# AIO_m_re_robotique_V3_2-PcPortableDany.net
KiCad netlist of a schematic drawn in EasyEDA
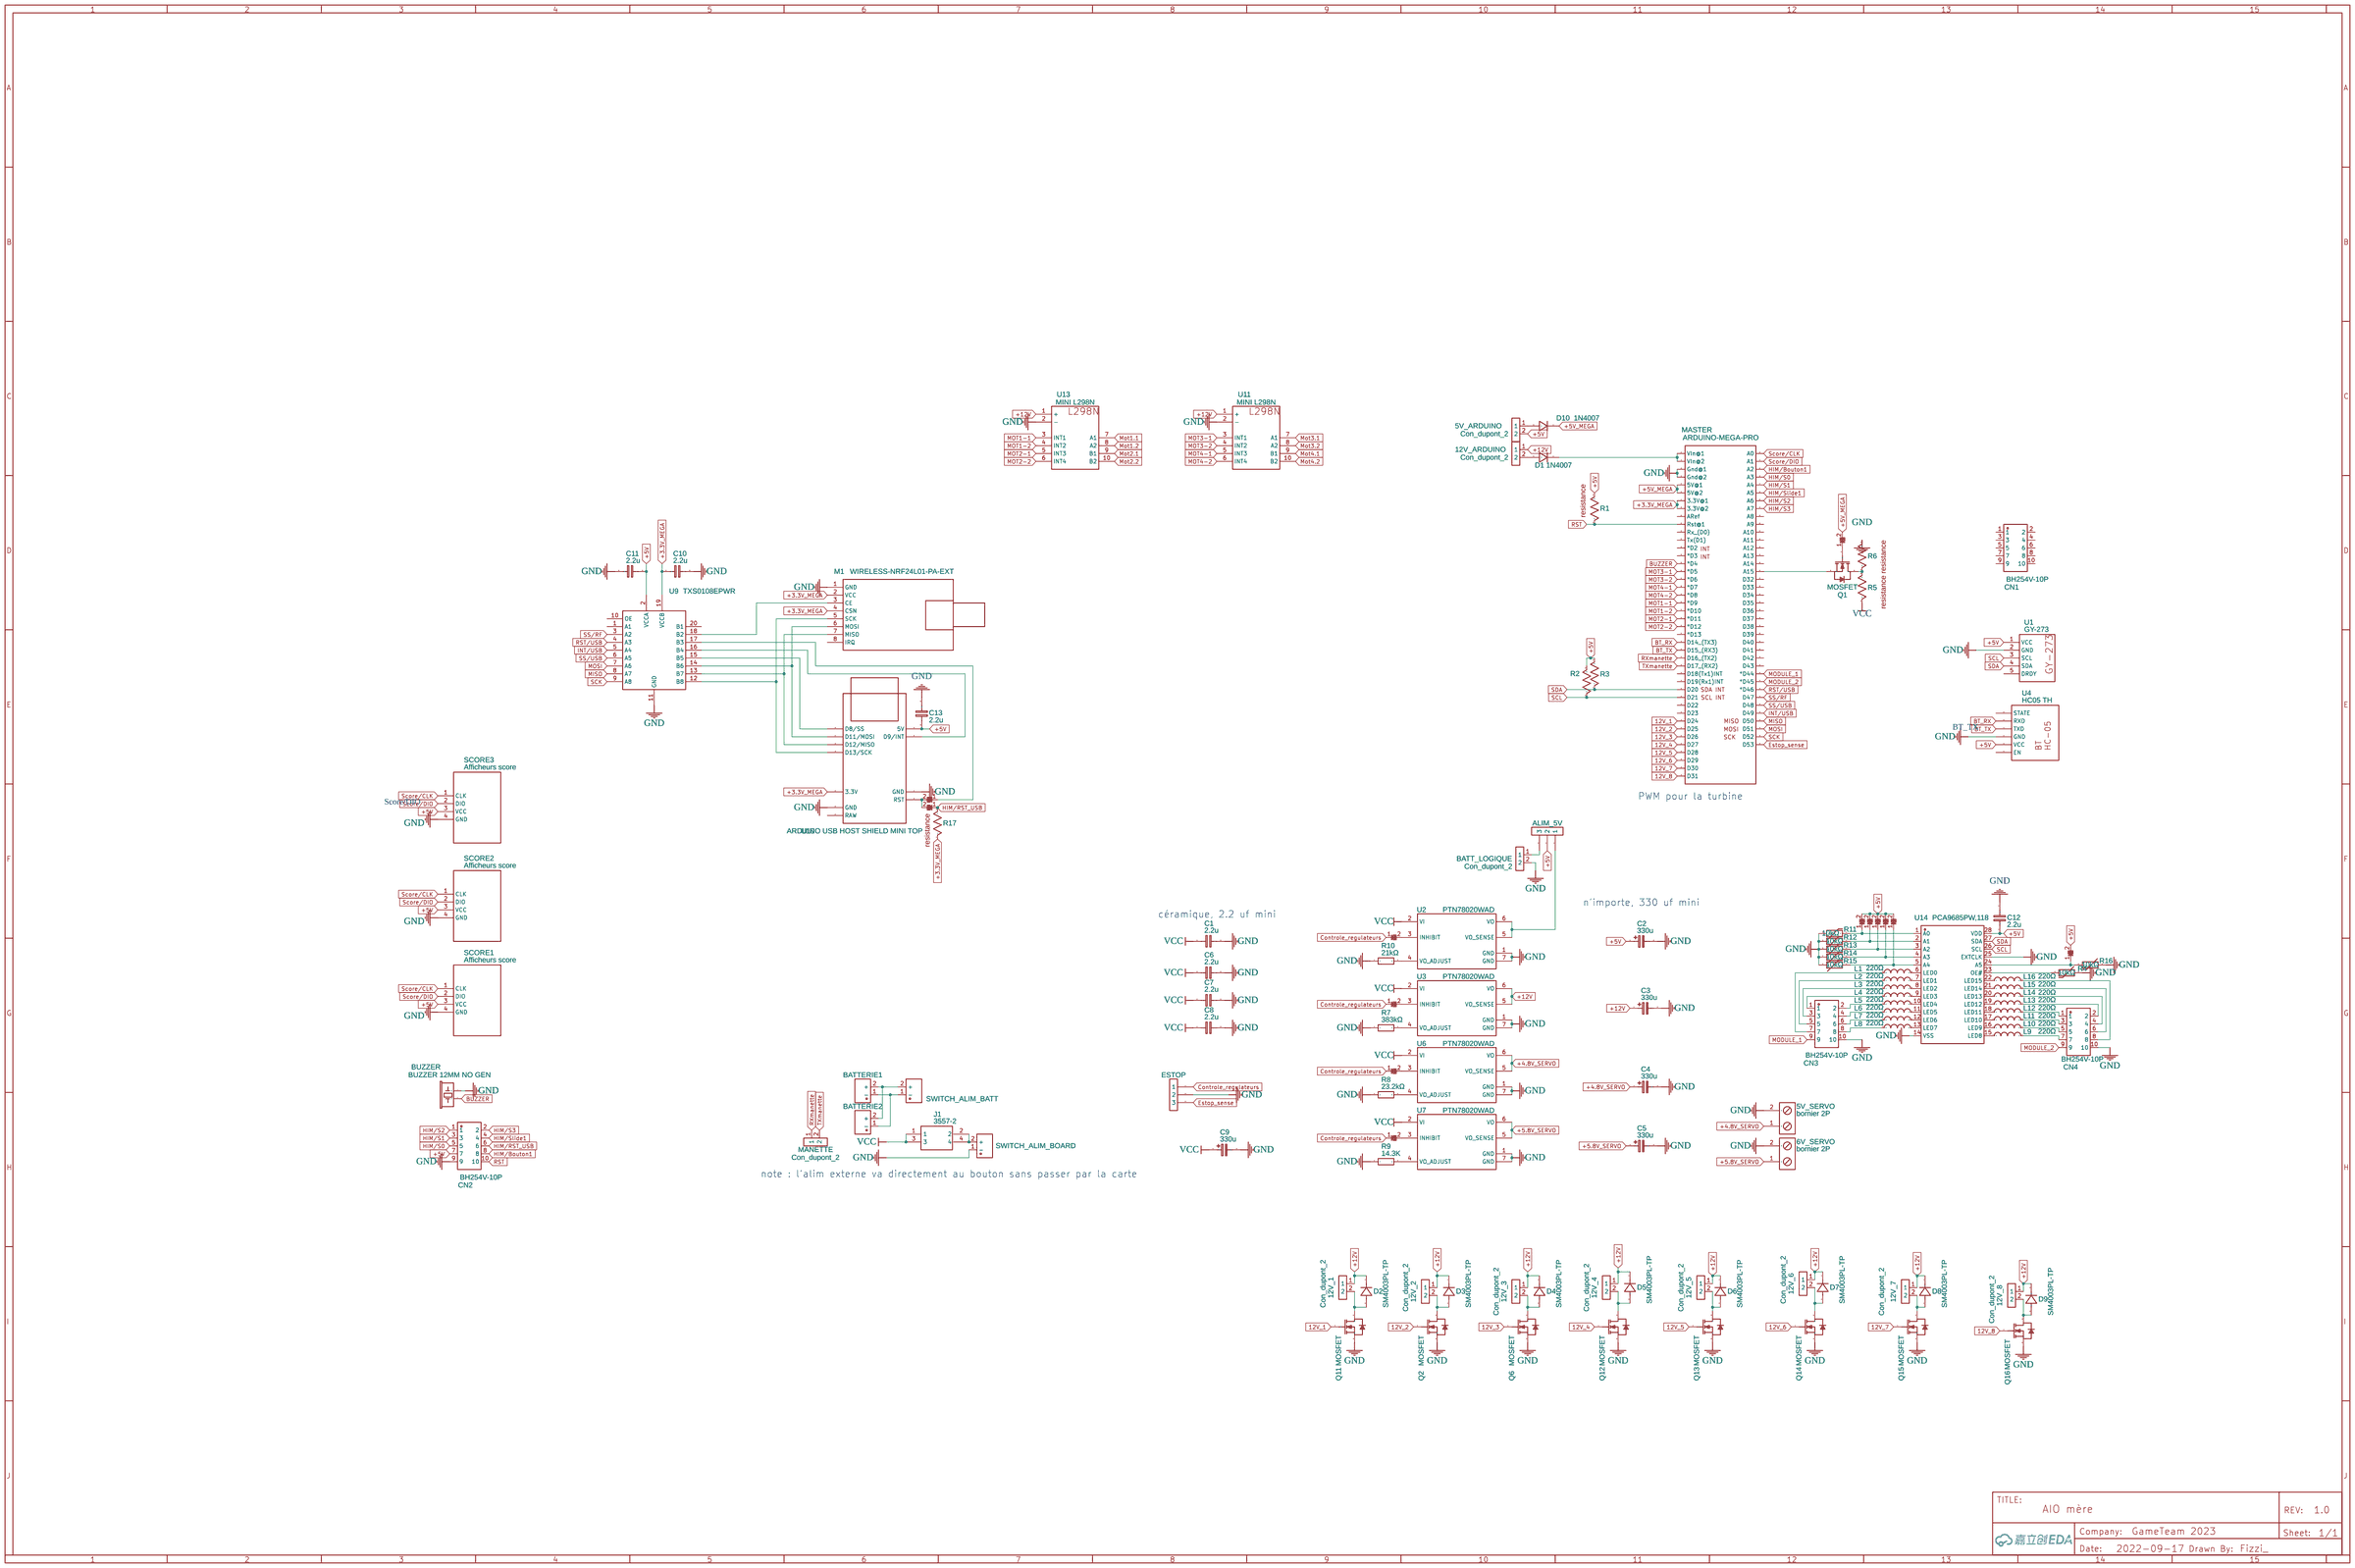
[diagram p0: schematic sheet]

(export (version "E")
  (design (tool "Eeschema 10.0.6"))
  (components
    (comp (ref "5V_ARDUINO") (value "Con_dupont_2") (libsource (lib "") (part "Con_dupont_2_2")))
    (comp (ref "5V_SERVO")
      (value "bornier 2P")
      (fields (field (name "BOM_Manufacturer Part") "bornier"))
      (libsource (lib "") (part "bornier 2P"))
    )
    (comp (ref "6V_SERVO")
      (value "bornier 2P")
      (fields (field (name "BOM_Manufacturer Part") "bornier"))
      (libsource (lib "") (part "bornier 2P_1"))
    )
    (comp (ref "12V_1") (value "Con_dupont_2") (libsource (lib "") (part "Con_dupont_2_1")))
    (comp (ref "12V_2") (value "Con_dupont_2") (libsource (lib "") (part "Con_dupont_2_1")))
    (comp (ref "12V_3") (value "Con_dupont_2") (libsource (lib "") (part "Con_dupont_2_1")))
    (comp (ref "12V_4") (value "Con_dupont_2") (libsource (lib "") (part "Con_dupont_2_1")))
    (comp (ref "12V_5") (value "Con_dupont_2") (libsource (lib "") (part "Con_dupont_2_1")))
    (comp (ref "12V_6") (value "Con_dupont_2") (libsource (lib "") (part "Con_dupont_2_1")))
    (comp (ref "12V_7") (value "Con_dupont_2") (libsource (lib "") (part "Con_dupont_2_1")))
    (comp (ref "12V_8") (value "Con_dupont_2") (libsource (lib "") (part "Con_dupont_2_1")))
    (comp (ref "12V_ARDUINO") (value "Con_dupont_2") (libsource (lib "") (part "Con_dupont_2_4")))
    (comp (ref "ALIM_5V") (value "Dupont 3Pin") (libsource (lib "") (part "Dupont 3Pin")))
    (comp (ref "BATTERIE1")
      (value "XT60-M")
      (fields
        (field (name "BOM_Manufacturer Part") "XT60UPB-M")
        (field (name "BOM_Supplier Part") "C2918078")
      )
      (libsource (lib "") (part "XT60-M_1"))
    )
    (comp (ref "BATTERIE2")
      (value "XT60-M")
      (fields
        (field (name "BOM_Manufacturer Part") "XT60UPB-M")
        (field (name "BOM_Supplier Part") "C2918078")
      )
      (libsource (lib "") (part "XT60-M_1"))
    )
    (comp (ref "BATT_LOGIQUE") (value "Con_dupont_2") (libsource (lib "") (part "Con_dupont_2_3")))
    (comp (ref "BUZZER") (value "BUZZER 12MM NO GEN") (libsource (lib "") (part "BUZZER 12MM NO GEN")))
    (comp (ref "BYPASS1") (value "SolderJumper") (libsource (lib "") (part "SolderJumperSmd6030")))
    (comp (ref "BYPASS2") (value "SolderJumper") (libsource (lib "") (part "SolderJumperSmd6030")))
    (comp (ref "BYPASS3") (value "SolderJumper") (libsource (lib "") (part "SolderJumperSmd6030")))
    (comp (ref "BYPASS4") (value "SolderJumper") (libsource (lib "") (part "SolderJumperSmd6030")))
    (comp (ref "BYPASS5") (value "SolderJumper") (libsource (lib "") (part "SolderJumperSmd6030")))
    (comp (ref "BYPASS6") (value "SolderJumper") (libsource (lib "") (part "SolderJumperSmd6030")))
    (comp (ref "BYPASS7") (value "SolderJumper") (libsource (lib "") (part "SolderJumperSmd6030")))
    (comp (ref "BYPASS8") (value "SolderJumper") (libsource (lib "") (part "SolderJumperSmd6030_2")))
    (comp (ref "BYPASS9") (value "SolderJumper") (libsource (lib "") (part "SolderJumperSmd6030_2")))
    (comp (ref "C1") (value "2.2u") (libsource (lib "") (part "C_0805_EU_1")))
    (comp (ref "C2") (value "330u") (libsource (lib "") (part "CE_TH_D8.0×F3.5_EU")))
    (comp (ref "C3") (value "330u") (libsource (lib "") (part "CE_TH_D8.0×F3.5_EU")))
    (comp (ref "C4") (value "330u") (libsource (lib "") (part "CE_TH_D8.0×F3.5_EU")))
    (comp (ref "C5") (value "330u") (libsource (lib "") (part "CE_TH_D8.0×F3.5_EU")))
    (comp (ref "C6") (value "2.2u") (libsource (lib "") (part "C_0805_EU_1")))
    (comp (ref "C7") (value "2.2u") (libsource (lib "") (part "C_0805_EU_1")))
    (comp (ref "C8") (value "2.2u") (libsource (lib "") (part "C_0805_EU_1")))
    (comp (ref "C9") (value "330u") (libsource (lib "") (part "CE_TH_D8.0×F3.5_EU")))
    (comp (ref "C10") (value "2.2u") (libsource (lib "") (part "C_0805_EU")))
    (comp (ref "C11") (value "2.2u") (libsource (lib "") (part "C_0805_EU")))
    (comp (ref "C12") (value "2.2u") (libsource (lib "") (part "C_0805_EU_2")))
    (comp (ref "C13") (value "2.2u") (libsource (lib "") (part "C_0805_EU_3")))
    (comp (ref "CN1")
      (value "BH254V-10P")
      (fields (field (name "BOM_Supplier Part") "C492442"))
      (libsource (lib "") (part "BH254V-10P"))
    )
    (comp (ref "CN2")
      (value "BH254V-10P")
      (fields (field (name "BOM_Supplier Part") "C492442"))
      (libsource (lib "") (part "BH254V-10P"))
    )
    (comp (ref "CN3")
      (value "BH254V-10P")
      (fields (field (name "BOM_Supplier Part") "C492442"))
      (libsource (lib "") (part "BH254V-10P"))
    )
    (comp (ref "CN4")
      (value "BH254V-10P")
      (fields (field (name "BOM_Supplier Part") "C492442"))
      (libsource (lib "") (part "BH254V-10P"))
    )
    (comp (ref "D1")
      (value "1N4007")
      (fields (field (name "BOM_Supplier Part") "C106903"))
      (libsource (lib "") (part "1N4007"))
    )
    (comp (ref "D2")
      (value "SM4003PL-TP")
      (fields (field (name "BOM_Supplier Part") "C725472"))
      (libsource (lib "") (part "SM4003PL-TP"))
    )
    (comp (ref "D3")
      (value "SM4003PL-TP")
      (fields (field (name "BOM_Supplier Part") "C725472"))
      (libsource (lib "") (part "SM4003PL-TP"))
    )
    (comp (ref "D4")
      (value "SM4003PL-TP")
      (fields (field (name "BOM_Supplier Part") "C725472"))
      (libsource (lib "") (part "SM4003PL-TP"))
    )
    (comp (ref "D5")
      (value "SM4003PL-TP")
      (fields (field (name "BOM_Supplier Part") "C725472"))
      (libsource (lib "") (part "SM4003PL-TP"))
    )
    (comp (ref "D6")
      (value "SM4003PL-TP")
      (fields (field (name "BOM_Supplier Part") "C725472"))
      (libsource (lib "") (part "SM4003PL-TP"))
    )
    (comp (ref "D7")
      (value "SM4003PL-TP")
      (fields (field (name "BOM_Supplier Part") "C725472"))
      (libsource (lib "") (part "SM4003PL-TP"))
    )
    (comp (ref "D8")
      (value "SM4003PL-TP")
      (fields (field (name "BOM_Supplier Part") "C725472"))
      (libsource (lib "") (part "SM4003PL-TP"))
    )
    (comp (ref "D9")
      (value "SM4003PL-TP")
      (fields (field (name "BOM_Supplier Part") "C725472"))
      (libsource (lib "") (part "SM4003PL-TP"))
    )
    (comp (ref "D10")
      (value "1N4007")
      (fields (field (name "BOM_Supplier Part") "C106903"))
      (libsource (lib "") (part "1N4007"))
    )
    (comp (ref "ENABP3") (value "SolderJumper") (libsource (lib "") (part "SolderJumperSmd6030_1")))
    (comp (ref "ENABP4") (value "SolderJumper") (libsource (lib "") (part "SolderJumperSmd6030_1")))
    (comp (ref "ENABP5") (value "SolderJumper") (libsource (lib "") (part "SolderJumperSmd6030_1")))
    (comp (ref "ENABP6") (value "SolderJumper") (libsource (lib "") (part "SolderJumperSmd6030_1")))
    (comp (ref "ESTOP") (value "Dupont 3Pin") (libsource (lib "") (part "Dupont 3Pin_1")))
    (comp (ref "J1") (value "3557-2") (libsource (lib "") (part "3557-2")))
    (comp (ref "L1")
      (value "220Ω")
      (fields
        (field (name "BOM_Manufacturer Part") "BLM18SG221TN1D")
        (field (name "BOM_Supplier Part") "C88988")
      )
      (libsource (lib "") (part "BLM18SG221TN1D"))
    )
    (comp (ref "L2")
      (value "220Ω")
      (fields
        (field (name "BOM_Manufacturer Part") "BLM18SG221TN1D")
        (field (name "BOM_Supplier Part") "C88988")
      )
      (libsource (lib "") (part "BLM18SG221TN1D"))
    )
    (comp (ref "L3")
      (value "220Ω")
      (fields
        (field (name "BOM_Manufacturer Part") "BLM18SG221TN1D")
        (field (name "BOM_Supplier Part") "C88988")
      )
      (libsource (lib "") (part "BLM18SG221TN1D"))
    )
    (comp (ref "L4")
      (value "220Ω")
      (fields
        (field (name "BOM_Manufacturer Part") "BLM18SG221TN1D")
        (field (name "BOM_Supplier Part") "C88988")
      )
      (libsource (lib "") (part "BLM18SG221TN1D"))
    )
    (comp (ref "L5")
      (value "220Ω")
      (fields
        (field (name "BOM_Manufacturer Part") "BLM18SG221TN1D")
        (field (name "BOM_Supplier Part") "C88988")
      )
      (libsource (lib "") (part "BLM18SG221TN1D"))
    )
    (comp (ref "L6")
      (value "220Ω")
      (fields
        (field (name "BOM_Manufacturer Part") "BLM18SG221TN1D")
        (field (name "BOM_Supplier Part") "C88988")
      )
      (libsource (lib "") (part "BLM18SG221TN1D"))
    )
    (comp (ref "L7")
      (value "220Ω")
      (fields
        (field (name "BOM_Manufacturer Part") "BLM18SG221TN1D")
        (field (name "BOM_Supplier Part") "C88988")
      )
      (libsource (lib "") (part "BLM18SG221TN1D"))
    )
    (comp (ref "L8")
      (value "220Ω")
      (fields
        (field (name "BOM_Manufacturer Part") "BLM18SG221TN1D")
        (field (name "BOM_Supplier Part") "C88988")
      )
      (libsource (lib "") (part "BLM18SG221TN1D"))
    )
    (comp (ref "L9")
      (value "220Ω")
      (fields
        (field (name "BOM_Manufacturer Part") "BLM18SG221TN1D")
        (field (name "BOM_Supplier Part") "C88988")
      )
      (libsource (lib "") (part "BLM18SG221TN1D"))
    )
    (comp (ref "L10")
      (value "220Ω")
      (fields
        (field (name "BOM_Manufacturer Part") "BLM18SG221TN1D")
        (field (name "BOM_Supplier Part") "C88988")
      )
      (libsource (lib "") (part "BLM18SG221TN1D"))
    )
    (comp (ref "L11")
      (value "220Ω")
      (fields
        (field (name "BOM_Manufacturer Part") "BLM18SG221TN1D")
        (field (name "BOM_Supplier Part") "C88988")
      )
      (libsource (lib "") (part "BLM18SG221TN1D"))
    )
    (comp (ref "L12")
      (value "220Ω")
      (fields
        (field (name "BOM_Manufacturer Part") "BLM18SG221TN1D")
        (field (name "BOM_Supplier Part") "C88988")
      )
      (libsource (lib "") (part "BLM18SG221TN1D"))
    )
    (comp (ref "L13")
      (value "220Ω")
      (fields
        (field (name "BOM_Manufacturer Part") "BLM18SG221TN1D")
        (field (name "BOM_Supplier Part") "C88988")
      )
      (libsource (lib "") (part "BLM18SG221TN1D"))
    )
    (comp (ref "L14")
      (value "220Ω")
      (fields
        (field (name "BOM_Manufacturer Part") "BLM18SG221TN1D")
        (field (name "BOM_Supplier Part") "C88988")
      )
      (libsource (lib "") (part "BLM18SG221TN1D"))
    )
    (comp (ref "L15")
      (value "220Ω")
      (fields
        (field (name "BOM_Manufacturer Part") "BLM18SG221TN1D")
        (field (name "BOM_Supplier Part") "C88988")
      )
      (libsource (lib "") (part "BLM18SG221TN1D"))
    )
    (comp (ref "L16")
      (value "220Ω")
      (fields
        (field (name "BOM_Manufacturer Part") "BLM18SG221TN1D")
        (field (name "BOM_Supplier Part") "C88988")
      )
      (libsource (lib "") (part "BLM18SG221TN1D"))
    )
    (comp (ref "M1")
      (value "WIRELESS-NRF24L01-PA-EXT")
      (libsource (lib "") (part "WIRELESS-NRF24L01-PA-EXT"))
    )
    (comp (ref "MANETTE") (value "Con_dupont_2") (libsource (lib "") (part "Con_dupont_2")))
    (comp (ref "MASTER")
      (value "ARDUINO-MEGA-PRO")
      (fields (field (name "BOM_Manufacturer Part") "ARDUINO MEGA 2560 PRO EMBED"))
      (libsource (lib "") (part "ARDUINO-MEGA-PRO COPY"))
    )
    (comp (ref "Q1") (value "MOSFET") (libsource (lib "") (part "MOSFET_1")))
    (comp (ref "Q2") (value "MOSFET") (libsource (lib "") (part "MOSFET")))
    (comp (ref "Q6") (value "MOSFET") (libsource (lib "") (part "MOSFET")))
    (comp (ref "Q11") (value "MOSFET") (libsource (lib "") (part "MOSFET")))
    (comp (ref "Q12") (value "MOSFET") (libsource (lib "") (part "MOSFET")))
    (comp (ref "Q13") (value "MOSFET") (libsource (lib "") (part "MOSFET")))
    (comp (ref "Q14") (value "MOSFET") (libsource (lib "") (part "MOSFET")))
    (comp (ref "Q15") (value "MOSFET") (libsource (lib "") (part "MOSFET")))
    (comp (ref "Q16") (value "MOSFET") (libsource (lib "") (part "MOSFET")))
    (comp (ref "R1") (value "1K") (libsource (lib "") (part "TROUGH HOLE RESISTOR 12MM_4")))
    (comp (ref "R2") (value "1K") (libsource (lib "") (part "TROUGH HOLE RESISTOR 12MM_3")))
    (comp (ref "R3") (value "1K") (libsource (lib "") (part "TROUGH HOLE RESISTOR 12MM_3")))
    (comp (ref "R4")
      (value "10kΩ")
      (fields
        (field (name "BOM_Manufacturer Part") "SDNT1608X103J3450HTF")
        (field (name "BOM_Supplier Part") "C43113")
      )
      (libsource (lib "") (part "SDNT1608X103J3450HTF"))
    )
    (comp (ref "R5") (value "1K") (libsource (lib "") (part "TROUGH HOLE RESISTOR 12MM")))
    (comp (ref "R6") (value "1K") (libsource (lib "") (part "TROUGH HOLE RESISTOR 12MM_1")))
    (comp (ref "R7")
      (value "383kΩ")
      (fields
        (field (name "BOM_Manufacturer Part") "TR0603D383KP0515")
        (field (name "BOM_Supplier Part") "C153382")
      )
      (libsource (lib "") (part "TR0603D383KP0515"))
    )
    (comp (ref "R8")
      (value "23.2kΩ")
      (fields
        (field (name "BOM_Manufacturer Part") "0603WAF2322T5E")
        (field (name "BOM_Supplier Part") "C23346")
      )
      (libsource (lib "") (part "0603WAF2322T5E"))
    )
    (comp (ref "R9")
      (value "14.3K")
      (fields
        (field (name "BOM_Manufacturer Part") "AC0603FR-0714K3L")
        (field (name "BOM_Supplier Part") "C227592")
      )
      (libsource (lib "") (part "AC0603FR-0714K3L"))
    )
    (comp (ref "R10")
      (value "21kΩ")
      (fields
        (field (name "BOM_Manufacturer Part") "HPCR0603F21K0K9")
        (field (name "BOM_Supplier Part") "C365119")
      )
      (libsource (lib "") (part "HPCR0603F21K0K9"))
    )
    (comp (ref "R11")
      (value "10kΩ")
      (fields
        (field (name "BOM_Manufacturer Part") "SDNT1608X103J3450HTF")
        (field (name "BOM_Supplier Part") "C43113")
      )
      (libsource (lib "") (part "SDNT1608X103J3450HTF_1"))
    )
    (comp (ref "R12")
      (value "10kΩ")
      (fields
        (field (name "BOM_Manufacturer Part") "SDNT1608X103J3450HTF")
        (field (name "BOM_Supplier Part") "C43113")
      )
      (libsource (lib "") (part "SDNT1608X103J3450HTF_1"))
    )
    (comp (ref "R13")
      (value "10kΩ")
      (fields
        (field (name "BOM_Manufacturer Part") "SDNT1608X103J3450HTF")
        (field (name "BOM_Supplier Part") "C43113")
      )
      (libsource (lib "") (part "SDNT1608X103J3450HTF_1"))
    )
    (comp (ref "R14")
      (value "10kΩ")
      (fields
        (field (name "BOM_Manufacturer Part") "SDNT1608X103J3450HTF")
        (field (name "BOM_Supplier Part") "C43113")
      )
      (libsource (lib "") (part "SDNT1608X103J3450HTF_1"))
    )
    (comp (ref "R15")
      (value "10kΩ")
      (fields
        (field (name "BOM_Manufacturer Part") "SDNT1608X103J3450HTF")
        (field (name "BOM_Supplier Part") "C43113")
      )
      (libsource (lib "") (part "SDNT1608X103J3450HTF_1"))
    )
    (comp (ref "R16")
      (value "10kΩ")
      (fields
        (field (name "BOM_Manufacturer Part") "SDNT1608X103J3450HTF")
        (field (name "BOM_Supplier Part") "C43113")
      )
      (libsource (lib "") (part "SDNT1608X103J3450HTF"))
    )
    (comp (ref "R17") (value "1K") (libsource (lib "") (part "TROUGH HOLE RESISTOR 12MM_2")))
    (comp (ref "SCORE1") (value "Afficheurs score") (libsource (lib "") (part "GROVE-2MM-4PIN-I2C")))
    (comp (ref "SCORE2") (value "Afficheurs score") (libsource (lib "") (part "GROVE-2MM-4PIN-I2C")))
    (comp (ref "SCORE3") (value "Afficheurs score") (libsource (lib "") (part "GROVE-2MM-4PIN-I2C")))
    (comp (ref "SWITCH_ALIM_BATT")
      (value "XT60-M")
      (fields
        (field (name "BOM_Manufacturer Part") "XT60UPB-M")
        (field (name "BOM_Supplier Part") "C2918078")
      )
      (libsource (lib "") (part "XT60-M"))
    )
    (comp (ref "SWITCH_ALIM_BOARD")
      (value "XT60-M")
      (fields
        (field (name "BOM_Manufacturer Part") "XT60UPB-M")
        (field (name "BOM_Supplier Part") "C2918078")
      )
      (libsource (lib "") (part "XT60-M_2"))
    )
    (comp (ref "U1") (value "GY-273") (libsource (lib "") (part "GY-273")))
    (comp (ref "U2") (value "PTN78020WAD") (libsource (lib "") (part "PTN78020WAD")))
    (comp (ref "U3") (value "PTN78020WAD") (libsource (lib "") (part "PTN78020WAD")))
    (comp (ref "U4") (value "HC05 TH") (libsource (lib "") (part "HC05 TH")))
    (comp (ref "U6") (value "PTN78020WAD") (libsource (lib "") (part "PTN78020WAD")))
    (comp (ref "U7") (value "PTN78020WAD") (libsource (lib "") (part "PTN78020WAD")))
    (comp (ref "U9")
      (value "TXS0108EPWR")
      (fields (field (name "BOM_Supplier Part") "C17206"))
      (libsource (lib "") (part "TXS0108EPWR"))
    )
    (comp (ref "U10")
      (value "ARDUINO USB HOST SHIELD MINI TOP")
      (libsource (lib "") (part "ARDUINO USB HOST SHIELD MINI TOP"))
    )
    (comp (ref "U11") (value "MINI L298N") (libsource (lib "") (part "MINI L298N")))
    (comp (ref "U13") (value "MINI L298N") (libsource (lib "") (part "MINI L298N")))
    (comp (ref "U14")
      (value "PCA9685PW,118")
      (fields (field (name "BOM_Supplier Part") "C2678753"))
      (libsource (lib "") (part "PCA9685PW,118"))
    )
  )
  (nets
    (net (code "1") (name "+3.3V_MEGA") (class "Default")
      (node (ref "C10") (pin "1") (pinfunction "1_1") (pintype "unspecified"))
      (node (ref "M1") (pin "2") (pinfunction "VCC_2") (pintype "passive"))
      (node (ref "M1") (pin "4") (pinfunction "CSN_4") (pintype "unspecified"))
      (node (ref "MASTER") (pin "7") (pinfunction "3.3V@1_7") (pintype "unspecified"))
      (node (ref "MASTER") (pin "8") (pinfunction "3.3V@2_8") (pintype "unspecified"))
      (node (ref "R17") (pin "1") (pinfunction "1_1") (pintype "unspecified"))
      (node (ref "U10") (pin "21") (pinfunction "3.3V_21") (pintype "unspecified"))
      (node (ref "U9") (pin "19") (pinfunction "VCCB_19") (pintype "unspecified"))
    )
    (net (code "2") (name "+4.8V_SERVO") (class "Default")
      (node (ref "5V_SERVO") (pin "1") (pinfunction "1_1") (pintype "unspecified"))
      (node (ref "C4") (pin "1") (pinfunction "1_1") (pintype "unspecified"))
      (node (ref "U6") (pin "5") (pinfunction "VO_SENSE_5") (pintype "unspecified"))
      (node (ref "U6") (pin "6") (pinfunction "VO_6") (pintype "passive"))
    )
    (net (code "3") (name "+5.8V_SERVO") (class "Default")
      (node (ref "6V_SERVO") (pin "1") (pinfunction "1_1") (pintype "unspecified"))
      (node (ref "C5") (pin "1") (pinfunction "1_1") (pintype "unspecified"))
      (node (ref "U7") (pin "5") (pinfunction "VO_SENSE_5") (pintype "unspecified"))
      (node (ref "U7") (pin "6") (pinfunction "VO_6") (pintype "passive"))
    )
    (net (code "4") (name "+5V") (class "Default")
      (node (ref "5V_ARDUINO") (pin "2") (pinfunction "2_2") (pintype "unspecified"))
      (node (ref "ALIM_5V") (pin "2") (pinfunction "2_2") (pintype "unspecified"))
      (node (ref "BYPASS1") (pin "2") (pinfunction "2_2") (pintype "unspecified"))
      (node (ref "BYPASS3") (pin "2") (pinfunction "2_2") (pintype "unspecified"))
      (node (ref "BYPASS4") (pin "2") (pinfunction "2_2") (pintype "unspecified"))
      (node (ref "BYPASS5") (pin "2") (pinfunction "2_2") (pintype "unspecified"))
      (node (ref "BYPASS6") (pin "2") (pinfunction "2_2") (pintype "unspecified"))
      (node (ref "BYPASS7") (pin "2") (pinfunction "2_2") (pintype "unspecified"))
      (node (ref "C11") (pin "2") (pinfunction "2_2") (pintype "unspecified"))
      (node (ref "C12") (pin "1") (pinfunction "1_1") (pintype "unspecified"))
      (node (ref "C13") (pin "1") (pinfunction "1_1") (pintype "unspecified"))
      (node (ref "C2") (pin "1") (pinfunction "1_1") (pintype "unspecified"))
      (node (ref "CN2") (pin "7") (pinfunction "7_7") (pintype "unspecified"))
      (node (ref "R1") (pin "2") (pinfunction "2_2") (pintype "unspecified"))
      (node (ref "R2") (pin "2") (pinfunction "2_2") (pintype "unspecified"))
      (node (ref "R3") (pin "2") (pinfunction "2_2") (pintype "unspecified"))
      (node (ref "SCORE1") (pin "3") (pinfunction "VCC_3") (pintype "unspecified"))
      (node (ref "SCORE2") (pin "3") (pinfunction "VCC_3") (pintype "unspecified"))
      (node (ref "SCORE3") (pin "3") (pinfunction "VCC_3") (pintype "unspecified"))
      (node (ref "U1") (pin "1") (pinfunction "VCC_1") (pintype "unspecified"))
      (node (ref "U10") (pin "25") (pinfunction "5V_25") (pintype "unspecified"))
      (node (ref "U14") (pin "28") (pinfunction "VDD_28") (pintype "unspecified"))
      (node (ref "U4") (pin "2") (pinfunction "VCC_2") (pintype "unspecified"))
      (node (ref "U9") (pin "2") (pinfunction "VCCA_2") (pintype "unspecified"))
    )
    (net (code "5") (name "+5V_MEGA") (class "Default")
      (node (ref "BYPASS2") (pin "2") (pinfunction "2_2") (pintype "unspecified"))
      (node (ref "D10") (pin "1") (pinfunction "1_1") (pintype "unspecified"))
      (node (ref "MASTER") (pin "5") (pinfunction "5V@1_5") (pintype "unspecified"))
      (node (ref "MASTER") (pin "6") (pinfunction "5V@2_6") (pintype "unspecified"))
    )
    (net (code "6") (name "+12V") (class "Default")
      (node (ref "12V_1") (pin "1") (pinfunction "1_1") (pintype "unspecified"))
      (node (ref "12V_2") (pin "1") (pinfunction "1_1") (pintype "unspecified"))
      (node (ref "12V_3") (pin "1") (pinfunction "1_1") (pintype "unspecified"))
      (node (ref "12V_4") (pin "1") (pinfunction "1_1") (pintype "unspecified"))
      (node (ref "12V_5") (pin "1") (pinfunction "1_1") (pintype "unspecified"))
      (node (ref "12V_6") (pin "1") (pinfunction "1_1") (pintype "unspecified"))
      (node (ref "12V_7") (pin "1") (pinfunction "1_1") (pintype "unspecified"))
      (node (ref "12V_8") (pin "1") (pinfunction "1_1") (pintype "unspecified"))
      (node (ref "12V_ARDUINO") (pin "1") (pinfunction "1_1") (pintype "unspecified"))
      (node (ref "C3") (pin "1") (pinfunction "1_1") (pintype "unspecified"))
      (node (ref "D2") (pin "1") (pinfunction "K_1") (pintype "unspecified"))
      (node (ref "D3") (pin "1") (pinfunction "K_1") (pintype "unspecified"))
      (node (ref "D4") (pin "1") (pinfunction "K_1") (pintype "unspecified"))
      (node (ref "D5") (pin "1") (pinfunction "K_1") (pintype "unspecified"))
      (node (ref "D6") (pin "1") (pinfunction "K_1") (pintype "unspecified"))
      (node (ref "D7") (pin "1") (pinfunction "K_1") (pintype "unspecified"))
      (node (ref "D8") (pin "1") (pinfunction "K_1") (pintype "unspecified"))
      (node (ref "D9") (pin "1") (pinfunction "K_1") (pintype "unspecified"))
      (node (ref "U11") (pin "1") (pinfunction "+_1") (pintype "unspecified"))
      (node (ref "U13") (pin "1") (pinfunction "+_1") (pintype "unspecified"))
      (node (ref "U3") (pin "5") (pinfunction "VO_SENSE_5") (pintype "unspecified"))
      (node (ref "U3") (pin "6") (pinfunction "VO_6") (pintype "passive"))
    )
    (net (code "7") (name "12V_1") (class "Default")
      (node (ref "MASTER") (pin "35") (pinfunction "D24_35") (pintype "unspecified"))
      (node (ref "Q11") (pin "1") (pinfunction "G_1") (pintype "unspecified"))
    )
    (net (code "8") (name "12V_2") (class "Default")
      (node (ref "MASTER") (pin "36") (pinfunction "D25_36") (pintype "unspecified"))
      (node (ref "Q2") (pin "1") (pinfunction "G_1") (pintype "unspecified"))
    )
    (net (code "9") (name "12V_3") (class "Default")
      (node (ref "MASTER") (pin "37") (pinfunction "D26_37") (pintype "unspecified"))
      (node (ref "Q6") (pin "1") (pinfunction "G_1") (pintype "unspecified"))
    )
    (net (code "10") (name "12V_4") (class "Default")
      (node (ref "MASTER") (pin "38") (pinfunction "D27_38") (pintype "unspecified"))
      (node (ref "Q12") (pin "1") (pinfunction "G_1") (pintype "unspecified"))
    )
    (net (code "11") (name "12V_5") (class "Default")
      (node (ref "MASTER") (pin "39") (pinfunction "D28_39") (pintype "unspecified"))
      (node (ref "Q13") (pin "1") (pinfunction "G_1") (pintype "unspecified"))
    )
    (net (code "12") (name "12V_6") (class "Default")
      (node (ref "MASTER") (pin "40") (pinfunction "D29_40") (pintype "unspecified"))
      (node (ref "Q14") (pin "1") (pinfunction "G_1") (pintype "unspecified"))
    )
    (net (code "13") (name "12V_7") (class "Default")
      (node (ref "MASTER") (pin "41") (pinfunction "D30_41") (pintype "unspecified"))
      (node (ref "Q15") (pin "1") (pinfunction "G_1") (pintype "unspecified"))
    )
    (net (code "14") (name "12V_8") (class "Default")
      (node (ref "MASTER") (pin "42") (pinfunction "D31_42") (pintype "unspecified"))
      (node (ref "Q16") (pin "1") (pinfunction "G_1") (pintype "unspecified"))
    )
    (net (code "15") (name "BT_RX") (class "Default")
      (node (ref "MASTER") (pin "25") (pinfunction "D14_(TX3)_25") (pintype "unspecified"))
      (node (ref "U4") (pin "5") (pinfunction "RXD_5") (pintype "unspecified"))
    )
    (net (code "16") (name "BT_TX") (class "Default")
      (node (ref "MASTER") (pin "26") (pinfunction "D15_(RX3)_26") (pintype "unspecified"))
      (node (ref "U4") (pin "4") (pinfunction "TXD_4") (pintype "unspecified"))
    )
    (net (code "17") (name "BUZZER") (class "Default")
      (node (ref "BUZZER") (pin "+") (pinfunction "1_+") (pintype "unspecified"))
      (node (ref "MASTER") (pin "15") (pinfunction "*D4_15") (pintype "unspecified"))
    )
    (net (code "18") (name "Controle_regulateurs") (class "Default")
      (node (ref "ENABP3") (pin "1") (pinfunction "1_1") (pintype "unspecified"))
      (node (ref "ENABP4") (pin "1") (pinfunction "1_1") (pintype "unspecified"))
      (node (ref "ENABP5") (pin "1") (pinfunction "1_1") (pintype "unspecified"))
      (node (ref "ENABP6") (pin "1") (pinfunction "1_1") (pintype "unspecified"))
      (node (ref "ESTOP") (pin "1") (pinfunction "1_1") (pintype "unspecified"))
    )
    (net (code "19") (name "Estop_sense") (class "Default")
      (node (ref "ESTOP") (pin "3") (pinfunction "3_3") (pintype "unspecified"))
      (node (ref "MASTER") (pin "80") (pinfunction "D53_80") (pintype "unspecified"))
    )
    (net (code "20") (name "GND") (class "Default")
      (node (ref "5V_SERVO") (pin "2") (pinfunction "2_2") (pintype "unspecified"))
      (node (ref "6V_SERVO") (pin "2") (pinfunction "2_2") (pintype "unspecified"))
      (node (ref "BATT_LOGIQUE") (pin "2") (pinfunction "2_2") (pintype "unspecified"))
      (node (ref "BUZZER") (pin "-") (pinfunction "2_-") (pintype "unspecified"))
      (node (ref "C1") (pin "2") (pinfunction "2_2") (pintype "unspecified"))
      (node (ref "C10") (pin "2") (pinfunction "2_2") (pintype "unspecified"))
      (node (ref "C11") (pin "1") (pinfunction "1_1") (pintype "unspecified"))
      (node (ref "C12") (pin "2") (pinfunction "2_2") (pintype "unspecified"))
      (node (ref "C13") (pin "2") (pinfunction "2_2") (pintype "unspecified"))
      (node (ref "C2") (pin "2") (pinfunction "2_2") (pintype "unspecified"))
      (node (ref "C3") (pin "2") (pinfunction "2_2") (pintype "unspecified"))
      (node (ref "C4") (pin "2") (pinfunction "2_2") (pintype "unspecified"))
      (node (ref "C5") (pin "2") (pinfunction "2_2") (pintype "unspecified"))
      (node (ref "C6") (pin "2") (pinfunction "2_2") (pintype "unspecified"))
      (node (ref "C7") (pin "2") (pinfunction "2_2") (pintype "unspecified"))
      (node (ref "C8") (pin "2") (pinfunction "2_2") (pintype "unspecified"))
      (node (ref "C9") (pin "2") (pinfunction "2_2") (pintype "unspecified"))
      (node (ref "CN2") (pin "9") (pinfunction "9_9") (pintype "unspecified"))
      (node (ref "CN3") (pin "10") (pinfunction "10_10") (pintype "unspecified"))
      (node (ref "CN4") (pin "10") (pinfunction "10_10") (pintype "unspecified"))
      (node (ref "ESTOP") (pin "2") (pinfunction "2_2") (pintype "unspecified"))
      (node (ref "M1") (pin "1") (pinfunction "GND_1") (pintype "passive"))
      (node (ref "MASTER") (pin "3") (pinfunction "Gnd@1_3") (pintype "unspecified"))
      (node (ref "MASTER") (pin "4") (pinfunction "Gnd@2_4") (pintype "unspecified"))
      (node (ref "Q11") (pin "3") (pinfunction "S_3") (pintype "unspecified"))
      (node (ref "Q12") (pin "3") (pinfunction "S_3") (pintype "unspecified"))
      (node (ref "Q13") (pin "3") (pinfunction "S_3") (pintype "unspecified"))
      (node (ref "Q14") (pin "3") (pinfunction "S_3") (pintype "unspecified"))
      (node (ref "Q15") (pin "3") (pinfunction "S_3") (pintype "unspecified"))
      (node (ref "Q16") (pin "3") (pinfunction "S_3") (pintype "unspecified"))
      (node (ref "Q2") (pin "3") (pinfunction "S_3") (pintype "unspecified"))
      (node (ref "Q6") (pin "3") (pinfunction "S_3") (pintype "unspecified"))
      (node (ref "R10") (pin "1") (pinfunction "1_1") (pintype "unspecified"))
      (node (ref "R11") (pin "2") (pinfunction "2_2") (pintype "input"))
      (node (ref "R12") (pin "2") (pinfunction "2_2") (pintype "input"))
      (node (ref "R13") (pin "2") (pinfunction "2_2") (pintype "input"))
      (node (ref "R14") (pin "2") (pinfunction "2_2") (pintype "input"))
      (node (ref "R15") (pin "2") (pinfunction "2_2") (pintype "input"))
      (node (ref "R16") (pin "2") (pinfunction "2_2") (pintype "input"))
      (node (ref "R4") (pin "2") (pinfunction "2_2") (pintype "input"))
      (node (ref "R6") (pin "2") (pinfunction "2_2") (pintype "unspecified"))
      (node (ref "R7") (pin "1") (pinfunction "1_1") (pintype "unspecified"))
      (node (ref "R8") (pin "1") (pinfunction "1_1") (pintype "input"))
      (node (ref "R9") (pin "1") (pinfunction "1_1") (pintype "unspecified"))
      (node (ref "SCORE1") (pin "4") (pinfunction "GND_4") (pintype "unspecified"))
      (node (ref "SCORE2") (pin "4") (pinfunction "GND_4") (pintype "unspecified"))
      (node (ref "SCORE3") (pin "4") (pinfunction "GND_4") (pintype "unspecified"))
      (node (ref "SWITCH_ALIM_BOARD") (pin "1") (pinfunction "-_1") (pintype "unspecified"))
      (node (ref "U1") (pin "2") (pinfunction "GND_2") (pintype "unspecified"))
      (node (ref "U10") (pin "23") (pinfunction "GND_23") (pintype "unspecified"))
      (node (ref "U10") (pin "4") (pinfunction "GND_4") (pintype "unspecified"))
      (node (ref "U11") (pin "2") (pinfunction "-_2") (pintype "unspecified"))
      (node (ref "U13") (pin "2") (pinfunction "-_2") (pintype "unspecified"))
      (node (ref "U14") (pin "14") (pinfunction "VSS_14") (pintype "unspecified"))
      (node (ref "U14") (pin "25") (pinfunction "EXTCLK_25") (pintype "unspecified"))
      (node (ref "U2") (pin "1") (pinfunction "GND_1") (pintype "passive"))
      (node (ref "U2") (pin "7") (pinfunction "GND_7") (pintype "passive"))
      (node (ref "U3") (pin "1") (pinfunction "GND_1") (pintype "passive"))
      (node (ref "U3") (pin "7") (pinfunction "GND_7") (pintype "passive"))
      (node (ref "U4") (pin "3") (pinfunction "GND_3") (pintype "unspecified"))
      (node (ref "U6") (pin "1") (pinfunction "GND_1") (pintype "passive"))
      (node (ref "U6") (pin "7") (pinfunction "GND_7") (pintype "passive"))
      (node (ref "U7") (pin "1") (pinfunction "GND_1") (pintype "passive"))
      (node (ref "U7") (pin "7") (pinfunction "GND_7") (pintype "passive"))
      (node (ref "U9") (pin "11") (pinfunction "GND_11") (pintype "unspecified"))
    )
    (net (code "21") (name "HIM{slash}Bouton1") (class "Default")
      (node (ref "CN2") (pin "8") (pinfunction "8_8") (pintype "unspecified"))
      (node (ref "MASTER") (pin "45") (pinfunction "A2_45") (pintype "unspecified"))
    )
    (net (code "22") (name "HIM{slash}RST_USB") (class "Default")
      (node (ref "BYPASS9") (pin "1") (pinfunction "1_1") (pintype "unspecified"))
      (node (ref "CN2") (pin "6") (pinfunction "6_6") (pintype "unspecified"))
      (node (ref "R17") (pin "2") (pinfunction "2_2") (pintype "unspecified"))
    )
    (net (code "23") (name "HIM{slash}S0") (class "Default")
      (node (ref "CN2") (pin "5") (pinfunction "5_5") (pintype "unspecified"))
      (node (ref "MASTER") (pin "46") (pinfunction "A3_46") (pintype "unspecified"))
    )
    (net (code "24") (name "HIM{slash}S1") (class "Default")
      (node (ref "CN2") (pin "3") (pinfunction "3_3") (pintype "unspecified"))
      (node (ref "MASTER") (pin "47") (pinfunction "A4_47") (pintype "unspecified"))
    )
    (net (code "25") (name "HIM{slash}S2") (class "Default")
      (node (ref "CN2") (pin "1") (pinfunction "1_1") (pintype "unspecified"))
      (node (ref "MASTER") (pin "49") (pinfunction "A6_49") (pintype "unspecified"))
    )
    (net (code "26") (name "HIM{slash}S3") (class "Default")
      (node (ref "CN2") (pin "2") (pinfunction "2_2") (pintype "unspecified"))
      (node (ref "MASTER") (pin "50") (pinfunction "A7_50") (pintype "unspecified"))
    )
    (net (code "27") (name "HIM{slash}Slide1") (class "Default")
      (node (ref "CN2") (pin "4") (pinfunction "4_4") (pintype "unspecified"))
      (node (ref "MASTER") (pin "48") (pinfunction "A5_48") (pintype "unspecified"))
    )
    (net (code "28") (name "INT{slash}USB") (class "Default")
      (node (ref "MASTER") (pin "76") (pinfunction "D49_76") (pintype "unspecified"))
      (node (ref "U9") (pin "5") (pinfunction "A4_5") (pintype "unspecified"))
    )
    (net (code "29") (name "MISO") (class "Default")
      (node (ref "MASTER") (pin "77") (pinfunction "D50_77") (pintype "unspecified"))
      (node (ref "U9") (pin "8") (pinfunction "A7_8") (pintype "unspecified"))
    )
    (net (code "30") (name "MODULE_1") (class "Default")
      (node (ref "CN3") (pin "9") (pinfunction "9_9") (pintype "unspecified"))
      (node (ref "MASTER") (pin "71") (pinfunction "*D44_71") (pintype "unspecified"))
    )
    (net (code "31") (name "MODULE_2") (class "Default")
      (node (ref "CN4") (pin "9") (pinfunction "9_9") (pintype "unspecified"))
      (node (ref "MASTER") (pin "72") (pinfunction "*D45_72") (pintype "unspecified"))
    )
    (net (code "32") (name "MOSI") (class "Default")
      (node (ref "MASTER") (pin "78") (pinfunction "D51_78") (pintype "unspecified"))
      (node (ref "U9") (pin "7") (pinfunction "A6_7") (pintype "unspecified"))
    )
    (net (code "33") (name "MOT1-1") (class "Default")
      (node (ref "MASTER") (pin "20") (pinfunction "*D9_20") (pintype "unspecified"))
      (node (ref "U13") (pin "3") (pinfunction "INT1_3") (pintype "unspecified"))
    )
    (net (code "34") (name "MOT1-2") (class "Default")
      (node (ref "MASTER") (pin "21") (pinfunction "*D10_21") (pintype "unspecified"))
      (node (ref "U13") (pin "4") (pinfunction "INT2_4") (pintype "unspecified"))
    )
    (net (code "35") (name "MOT2-1") (class "Default")
      (node (ref "MASTER") (pin "22") (pinfunction "*D11_22") (pintype "unspecified"))
      (node (ref "U13") (pin "5") (pinfunction "INT3_5") (pintype "unspecified"))
    )
    (net (code "36") (name "MOT2-2") (class "Default")
      (node (ref "MASTER") (pin "23") (pinfunction "*D12_23") (pintype "unspecified"))
      (node (ref "U13") (pin "6") (pinfunction "INT4_6") (pintype "unspecified"))
    )
    (net (code "37") (name "MOT3-1") (class "Default")
      (node (ref "MASTER") (pin "16") (pinfunction "*D5_16") (pintype "unspecified"))
      (node (ref "U11") (pin "3") (pinfunction "INT1_3") (pintype "unspecified"))
    )
    (net (code "38") (name "MOT3-2") (class "Default")
      (node (ref "MASTER") (pin "17") (pinfunction "*D6_17") (pintype "unspecified"))
      (node (ref "U11") (pin "4") (pinfunction "INT2_4") (pintype "unspecified"))
    )
    (net (code "39") (name "MOT4-1") (class "Default")
      (node (ref "MASTER") (pin "18") (pinfunction "*D7_18") (pintype "unspecified"))
      (node (ref "U11") (pin "5") (pinfunction "INT3_5") (pintype "unspecified"))
    )
    (net (code "40") (name "MOT4-2") (class "Default")
      (node (ref "MASTER") (pin "19") (pinfunction "*D8_19") (pintype "unspecified"))
      (node (ref "U11") (pin "6") (pinfunction "INT4_6") (pintype "unspecified"))
    )
    (net (code "41") (name "Mot1.1") (class "Default")
      (node (ref "U13") (pin "7") (pinfunction "A1_7") (pintype "unspecified"))
    )
    (net (code "42") (name "Mot1.2") (class "Default")
      (node (ref "U13") (pin "8") (pinfunction "A2_8") (pintype "unspecified"))
    )
    (net (code "43") (name "Mot2.1") (class "Default")
      (node (ref "U13") (pin "9") (pinfunction "B1_9") (pintype "unspecified"))
    )
    (net (code "44") (name "Mot2.2") (class "Default")
      (node (ref "U13") (pin "10") (pinfunction "B2_10") (pintype "unspecified"))
    )
    (net (code "45") (name "Mot3.1") (class "Default")
      (node (ref "U11") (pin "7") (pinfunction "A1_7") (pintype "unspecified"))
    )
    (net (code "46") (name "Mot3.2") (class "Default")
      (node (ref "U11") (pin "8") (pinfunction "A2_8") (pintype "unspecified"))
    )
    (net (code "47") (name "Mot4.1") (class "Default")
      (node (ref "U11") (pin "9") (pinfunction "B1_9") (pintype "unspecified"))
    )
    (net (code "48") (name "Mot4.2") (class "Default")
      (node (ref "U11") (pin "10") (pinfunction "B2_10") (pintype "unspecified"))
    )
    (net (code "49") (name "Net-(5V_ARDUINO-Pad1)") (class "Default")
      (node (ref "5V_ARDUINO") (pin "1") (pinfunction "1_1") (pintype "unspecified"))
      (node (ref "D10") (pin "2") (pinfunction "2_2") (pintype "unspecified"))
    )
    (net (code "50") (name "Net-(12V_ARDUINO-Pad2)") (class "Default")
      (node (ref "12V_ARDUINO") (pin "2") (pinfunction "2_2") (pintype "unspecified"))
      (node (ref "D1") (pin "2") (pinfunction "2_2") (pintype "unspecified"))
    )
    (net (code "51") (name "Net-(ALIM_5V-Pad3)") (class "Default")
      (node (ref "ALIM_5V") (pin "3") (pinfunction "3_3") (pintype "unspecified"))
      (node (ref "BATT_LOGIQUE") (pin "1") (pinfunction "1_1") (pintype "unspecified"))
    )
    (net (code "52") (name "Net-(BATTERIE1-+)") (class "Default")
      (node (ref "BATTERIE1") (pin "2") (pinfunction "+_2") (pintype "unspecified"))
      (node (ref "BATTERIE2") (pin "2") (pinfunction "+_2") (pintype "unspecified"))
      (node (ref "SWITCH_ALIM_BATT") (pin "2") (pinfunction "+_2") (pintype "unspecified"))
    )
    (net (code "53") (name "Net-(BATTERIE1--)") (class "Default")
      (node (ref "BATTERIE1") (pin "1") (pinfunction "-_1") (pintype "unspecified"))
      (node (ref "BATTERIE2") (pin "1") (pinfunction "-_1") (pintype "unspecified"))
      (node (ref "SWITCH_ALIM_BATT") (pin "1") (pinfunction "-_1") (pintype "unspecified"))
    )
    (net (code "54") (name "Net-(CN3-Pad1)") (class "Default")
      (node (ref "CN3") (pin "1") (pinfunction "1_1") (pintype "unspecified"))
      (node (ref "L4") (pin "1") (pinfunction "1_1") (pintype "unspecified"))
    )
    (net (code "55") (name "Net-(CN3-Pad2)") (class "Default")
      (node (ref "CN3") (pin "2") (pinfunction "2_2") (pintype "unspecified"))
      (node (ref "L5") (pin "1") (pinfunction "1_1") (pintype "unspecified"))
    )
    (net (code "56") (name "Net-(CN3-Pad3)") (class "Default")
      (node (ref "CN3") (pin "3") (pinfunction "3_3") (pintype "unspecified"))
      (node (ref "L3") (pin "1") (pinfunction "1_1") (pintype "unspecified"))
    )
    (net (code "57") (name "Net-(CN3-Pad4)") (class "Default")
      (node (ref "CN3") (pin "4") (pinfunction "4_4") (pintype "unspecified"))
      (node (ref "L6") (pin "1") (pinfunction "1_1") (pintype "unspecified"))
    )
    (net (code "58") (name "Net-(CN3-Pad5)") (class "Default")
      (node (ref "CN3") (pin "5") (pinfunction "5_5") (pintype "unspecified"))
      (node (ref "L2") (pin "1") (pinfunction "1_1") (pintype "unspecified"))
    )
    (net (code "59") (name "Net-(CN3-Pad6)") (class "Default")
      (node (ref "CN3") (pin "6") (pinfunction "6_6") (pintype "unspecified"))
      (node (ref "L7") (pin "1") (pinfunction "1_1") (pintype "unspecified"))
    )
    (net (code "60") (name "Net-(CN3-Pad7)") (class "Default")
      (node (ref "CN3") (pin "7") (pinfunction "7_7") (pintype "unspecified"))
      (node (ref "L1") (pin "1") (pinfunction "1_1") (pintype "unspecified"))
    )
    (net (code "61") (name "Net-(CN3-Pad8)") (class "Default")
      (node (ref "CN3") (pin "8") (pinfunction "8_8") (pintype "unspecified"))
      (node (ref "L8") (pin "1") (pinfunction "1_1") (pintype "unspecified"))
    )
    (net (code "62") (name "Net-(CN4-Pad1)") (class "Default")
      (node (ref "CN4") (pin "1") (pinfunction "1_1") (pintype "unspecified"))
      (node (ref "L12") (pin "2") (pinfunction "2_2") (pintype "unspecified"))
    )
    (net (code "63") (name "Net-(CN4-Pad2)") (class "Default")
      (node (ref "CN4") (pin "2") (pinfunction "2_2") (pintype "unspecified"))
      (node (ref "L13") (pin "2") (pinfunction "2_2") (pintype "unspecified"))
    )
    (net (code "64") (name "Net-(CN4-Pad3)") (class "Default")
      (node (ref "CN4") (pin "3") (pinfunction "3_3") (pintype "unspecified"))
      (node (ref "L11") (pin "2") (pinfunction "2_2") (pintype "unspecified"))
    )
    (net (code "65") (name "Net-(CN4-Pad4)") (class "Default")
      (node (ref "CN4") (pin "4") (pinfunction "4_4") (pintype "unspecified"))
      (node (ref "L14") (pin "2") (pinfunction "2_2") (pintype "unspecified"))
    )
    (net (code "66") (name "Net-(CN4-Pad5)") (class "Default")
      (node (ref "CN4") (pin "5") (pinfunction "5_5") (pintype "unspecified"))
      (node (ref "L10") (pin "2") (pinfunction "2_2") (pintype "unspecified"))
    )
    (net (code "67") (name "Net-(CN4-Pad6)") (class "Default")
      (node (ref "CN4") (pin "6") (pinfunction "6_6") (pintype "unspecified"))
      (node (ref "L15") (pin "2") (pinfunction "2_2") (pintype "unspecified"))
    )
    (net (code "68") (name "Net-(CN4-Pad7)") (class "Default")
      (node (ref "CN4") (pin "7") (pinfunction "7_7") (pintype "unspecified"))
      (node (ref "L9") (pin "2") (pinfunction "2_2") (pintype "unspecified"))
    )
    (net (code "69") (name "Net-(CN4-Pad8)") (class "Default")
      (node (ref "CN4") (pin "8") (pinfunction "8_8") (pintype "unspecified"))
      (node (ref "L16") (pin "2") (pinfunction "2_2") (pintype "unspecified"))
    )
    (net (code "70") (name "Net-(D2-A)") (class "Default")
      (node (ref "12V_1") (pin "2") (pinfunction "2_2") (pintype "unspecified"))
      (node (ref "D2") (pin "2") (pinfunction "A_2") (pintype "unspecified"))
      (node (ref "Q11") (pin "2") (pinfunction "D_2") (pintype "unspecified"))
    )
    (net (code "71") (name "Net-(D3-A)") (class "Default")
      (node (ref "12V_2") (pin "2") (pinfunction "2_2") (pintype "unspecified"))
      (node (ref "D3") (pin "2") (pinfunction "A_2") (pintype "unspecified"))
      (node (ref "Q2") (pin "2") (pinfunction "D_2") (pintype "unspecified"))
    )
    (net (code "72") (name "Net-(D4-A)") (class "Default")
      (node (ref "12V_3") (pin "2") (pinfunction "2_2") (pintype "unspecified"))
      (node (ref "D4") (pin "2") (pinfunction "A_2") (pintype "unspecified"))
      (node (ref "Q6") (pin "2") (pinfunction "D_2") (pintype "unspecified"))
    )
    (net (code "73") (name "Net-(D5-A)") (class "Default")
      (node (ref "12V_4") (pin "2") (pinfunction "2_2") (pintype "unspecified"))
      (node (ref "D5") (pin "2") (pinfunction "A_2") (pintype "unspecified"))
      (node (ref "Q12") (pin "2") (pinfunction "D_2") (pintype "unspecified"))
    )
    (net (code "74") (name "Net-(D6-A)") (class "Default")
      (node (ref "12V_5") (pin "2") (pinfunction "2_2") (pintype "unspecified"))
      (node (ref "D6") (pin "2") (pinfunction "A_2") (pintype "unspecified"))
      (node (ref "Q13") (pin "2") (pinfunction "D_2") (pintype "unspecified"))
    )
    (net (code "75") (name "Net-(D7-A)") (class "Default")
      (node (ref "12V_6") (pin "2") (pinfunction "2_2") (pintype "unspecified"))
      (node (ref "D7") (pin "2") (pinfunction "A_2") (pintype "unspecified"))
      (node (ref "Q14") (pin "2") (pinfunction "D_2") (pintype "unspecified"))
    )
    (net (code "76") (name "Net-(D8-A)") (class "Default")
      (node (ref "12V_7") (pin "2") (pinfunction "2_2") (pintype "unspecified"))
      (node (ref "D8") (pin "2") (pinfunction "A_2") (pintype "unspecified"))
      (node (ref "Q15") (pin "2") (pinfunction "D_2") (pintype "unspecified"))
    )
    (net (code "77") (name "Net-(D9-A)") (class "Default")
      (node (ref "12V_8") (pin "2") (pinfunction "2_2") (pintype "unspecified"))
      (node (ref "D9") (pin "2") (pinfunction "A_2") (pintype "unspecified"))
      (node (ref "Q16") (pin "2") (pinfunction "D_2") (pintype "unspecified"))
    )
    (net (code "78") (name "Net-(M1-CE)") (class "Default")
      (node (ref "M1") (pin "3") (pinfunction "CE_3") (pintype "unspecified"))
      (node (ref "U9") (pin "18") (pinfunction "B2_18") (pintype "unspecified"))
    )
    (net (code "79") (name "Net-(M1-MISO)") (class "Default")
      (node (ref "M1") (pin "7") (pinfunction "MISO_7") (pintype "unspecified"))
      (node (ref "U10") (pin "15") (pinfunction "D12/MISO_15") (pintype "unspecified"))
      (node (ref "U9") (pin "13") (pinfunction "B7_13") (pintype "unspecified"))
    )
    (net (code "80") (name "Net-(M1-MOSI)") (class "Default")
      (node (ref "M1") (pin "6") (pinfunction "MOSI_6") (pintype "unspecified"))
      (node (ref "U10") (pin "14") (pinfunction "D11/MOSI_14") (pintype "unspecified"))
      (node (ref "U9") (pin "14") (pinfunction "B6_14") (pintype "unspecified"))
    )
    (net (code "81") (name "Net-(M1-SCK)") (class "Default")
      (node (ref "M1") (pin "5") (pinfunction "SCK_5") (pintype "unspecified"))
      (node (ref "U10") (pin "16") (pinfunction "D13/SCK_16") (pintype "unspecified"))
      (node (ref "U9") (pin "12") (pinfunction "B8_12") (pintype "unspecified"))
    )
    (net (code "82") (name "Net-(MASTER-A15)") (class "Default")
      (node (ref "MASTER") (pin "58") (pinfunction "A15_58") (pintype "unspecified"))
      (node (ref "Q1") (pin "3") (pinfunction "S_3") (pintype "unspecified"))
    )
    (net (code "83") (name "Net-(MASTER-VIn@1)") (class "Default")
      (node (ref "D1") (pin "1") (pinfunction "1_1") (pintype "unspecified"))
      (node (ref "MASTER") (pin "1") (pinfunction "VIn@1_1") (pintype "unspecified"))
      (node (ref "MASTER") (pin "2") (pinfunction "VIn@2_2") (pintype "unspecified"))
    )
    (net (code "84") (name "Net-(Q1-D)") (class "Default")
      (node (ref "Q1") (pin "2") (pinfunction "D_2") (pintype "unspecified"))
      (node (ref "R5") (pin "2") (pinfunction "2_2") (pintype "unspecified"))
      (node (ref "R6") (pin "1") (pinfunction "1_1") (pintype "unspecified"))
    )
    (net (code "85") (name "Net-(Q1-G)") (class "Default")
      (node (ref "BYPASS2") (pin "1") (pinfunction "1_1") (pintype "unspecified"))
      (node (ref "Q1") (pin "1") (pinfunction "G_1") (pintype "unspecified"))
    )
    (net (code "86") (name "Net-(SWITCH_ALIM_BOARD-+)") (class "Default")
      (node (ref "J1") (pin "2") (pinfunction "2_2") (pintype "bidirectional"))
      (node (ref "J1") (pin "4") (pinfunction "4_4") (pintype "bidirectional"))
      (node (ref "SWITCH_ALIM_BOARD") (pin "2") (pinfunction "+_2") (pintype "unspecified"))
    )
    (net (code "87") (name "Net-(U2-INHIBIT)") (class "Default")
      (node (ref "ENABP3") (pin "2") (pinfunction "2_2") (pintype "unspecified"))
      (node (ref "U2") (pin "3") (pinfunction "INHIBIT_3") (pintype "unspecified"))
    )
    (net (code "88") (name "Net-(U2-VO)") (class "Default")
      (node (ref "ALIM_5V") (pin "1") (pinfunction "1_1") (pintype "unspecified"))
      (node (ref "U2") (pin "5") (pinfunction "VO_SENSE_5") (pintype "unspecified"))
      (node (ref "U2") (pin "6") (pinfunction "VO_6") (pintype "passive"))
    )
    (net (code "89") (name "Net-(U2-VO_ADJUST)") (class "Default")
      (node (ref "R10") (pin "2") (pinfunction "2_2") (pintype "unspecified"))
      (node (ref "U2") (pin "4") (pinfunction "VO_ADJUST_4") (pintype "unspecified"))
    )
    (net (code "90") (name "Net-(U3-INHIBIT)") (class "Default")
      (node (ref "ENABP4") (pin "2") (pinfunction "2_2") (pintype "unspecified"))
      (node (ref "U3") (pin "3") (pinfunction "INHIBIT_3") (pintype "unspecified"))
    )
    (net (code "91") (name "Net-(U3-VO_ADJUST)") (class "Default")
      (node (ref "R7") (pin "2") (pinfunction "2_2") (pintype "unspecified"))
      (node (ref "U3") (pin "4") (pinfunction "VO_ADJUST_4") (pintype "unspecified"))
    )
    (net (code "92") (name "Net-(U6-INHIBIT)") (class "Default")
      (node (ref "ENABP5") (pin "2") (pinfunction "2_2") (pintype "unspecified"))
      (node (ref "U6") (pin "3") (pinfunction "INHIBIT_3") (pintype "unspecified"))
    )
    (net (code "93") (name "Net-(U6-VO_ADJUST)") (class "Default")
      (node (ref "R8") (pin "2") (pinfunction "2_2") (pintype "input"))
      (node (ref "U6") (pin "4") (pinfunction "VO_ADJUST_4") (pintype "unspecified"))
    )
    (net (code "94") (name "Net-(U7-INHIBIT)") (class "Default")
      (node (ref "ENABP6") (pin "2") (pinfunction "2_2") (pintype "unspecified"))
      (node (ref "U7") (pin "3") (pinfunction "INHIBIT_3") (pintype "unspecified"))
    )
    (net (code "95") (name "Net-(U7-VO_ADJUST)") (class "Default")
      (node (ref "R9") (pin "2") (pinfunction "2_2") (pintype "unspecified"))
      (node (ref "U7") (pin "4") (pinfunction "VO_ADJUST_4") (pintype "unspecified"))
    )
    (net (code "96") (name "Net-(U9-B3)") (class "Default")
      (node (ref "BYPASS8") (pin "1") (pinfunction "1_1") (pintype "unspecified"))
      (node (ref "U9") (pin "17") (pinfunction "B3_17") (pintype "unspecified"))
    )
    (net (code "97") (name "Net-(U10-D8{slash}SS)") (class "Default")
      (node (ref "U10") (pin "13") (pinfunction "D8/SS_13") (pintype "unspecified"))
      (node (ref "U9") (pin "15") (pinfunction "B5_15") (pintype "unspecified"))
    )
    (net (code "98") (name "Net-(U10-D9{slash}INT)") (class "Default")
      (node (ref "U10") (pin "12") (pinfunction "D9/INT_12") (pintype "unspecified"))
      (node (ref "U9") (pin "16") (pinfunction "B4_16") (pintype "unspecified"))
    )
    (net (code "99") (name "Net-(U10-RST)") (class "Default")
      (node (ref "BYPASS8") (pin "2") (pinfunction "2_2") (pintype "unspecified"))
      (node (ref "BYPASS9") (pin "2") (pinfunction "2_2") (pintype "unspecified"))
      (node (ref "U10") (pin "3") (pinfunction "RST_3") (pintype "unspecified"))
    )
    (net (code "100") (name "Net-(U14-A0)") (class "Default")
      (node (ref "BYPASS1") (pin "1") (pinfunction "1_1") (pintype "unspecified"))
      (node (ref "R11") (pin "1") (pinfunction "1_1") (pintype "input"))
      (node (ref "U14") (pin "1") (pinfunction "A0_1") (pintype "unspecified"))
    )
    (net (code "101") (name "Net-(U14-A1)") (class "Default")
      (node (ref "BYPASS3") (pin "1") (pinfunction "1_1") (pintype "unspecified"))
      (node (ref "R12") (pin "1") (pinfunction "1_1") (pintype "input"))
      (node (ref "U14") (pin "2") (pinfunction "A1_2") (pintype "unspecified"))
    )
    (net (code "102") (name "Net-(U14-A2)") (class "Default")
      (node (ref "BYPASS4") (pin "1") (pinfunction "1_1") (pintype "unspecified"))
      (node (ref "R13") (pin "1") (pinfunction "1_1") (pintype "input"))
      (node (ref "U14") (pin "3") (pinfunction "A2_3") (pintype "unspecified"))
    )
    (net (code "103") (name "Net-(U14-A3)") (class "Default")
      (node (ref "BYPASS5") (pin "1") (pinfunction "1_1") (pintype "unspecified"))
      (node (ref "R14") (pin "1") (pinfunction "1_1") (pintype "input"))
      (node (ref "U14") (pin "4") (pinfunction "A3_4") (pintype "unspecified"))
    )
    (net (code "104") (name "Net-(U14-A4)") (class "Default")
      (node (ref "BYPASS6") (pin "1") (pinfunction "1_1") (pintype "unspecified"))
      (node (ref "R15") (pin "1") (pinfunction "1_1") (pintype "input"))
      (node (ref "U14") (pin "5") (pinfunction "A4_5") (pintype "unspecified"))
    )
    (net (code "105") (name "Net-(U14-A5)") (class "Default")
      (node (ref "BYPASS7") (pin "1") (pinfunction "1_1") (pintype "unspecified"))
      (node (ref "R16") (pin "1") (pinfunction "1_1") (pintype "input"))
      (node (ref "U14") (pin "24") (pinfunction "A5_24") (pintype "unspecified"))
    )
    (net (code "106") (name "Net-(U14-LED0)") (class "Default")
      (node (ref "L1") (pin "2") (pinfunction "2_2") (pintype "unspecified"))
      (node (ref "U14") (pin "6") (pinfunction "LED0_6") (pintype "unspecified"))
    )
    (net (code "107") (name "Net-(U14-LED1)") (class "Default")
      (node (ref "L2") (pin "2") (pinfunction "2_2") (pintype "unspecified"))
      (node (ref "U14") (pin "7") (pinfunction "LED1_7") (pintype "unspecified"))
    )
    (net (code "108") (name "Net-(U14-LED2)") (class "Default")
      (node (ref "L3") (pin "2") (pinfunction "2_2") (pintype "unspecified"))
      (node (ref "U14") (pin "8") (pinfunction "LED2_8") (pintype "unspecified"))
    )
    (net (code "109") (name "Net-(U14-LED3)") (class "Default")
      (node (ref "L4") (pin "2") (pinfunction "2_2") (pintype "unspecified"))
      (node (ref "U14") (pin "9") (pinfunction "LED3_9") (pintype "unspecified"))
    )
    (net (code "110") (name "Net-(U14-LED4)") (class "Default")
      (node (ref "L5") (pin "2") (pinfunction "2_2") (pintype "unspecified"))
      (node (ref "U14") (pin "10") (pinfunction "LED4_10") (pintype "unspecified"))
    )
    (net (code "111") (name "Net-(U14-LED5)") (class "Default")
      (node (ref "L6") (pin "2") (pinfunction "2_2") (pintype "unspecified"))
      (node (ref "U14") (pin "11") (pinfunction "LED5_11") (pintype "unspecified"))
    )
    (net (code "112") (name "Net-(U14-LED6)") (class "Default")
      (node (ref "L7") (pin "2") (pinfunction "2_2") (pintype "unspecified"))
      (node (ref "U14") (pin "12") (pinfunction "LED6_12") (pintype "unspecified"))
    )
    (net (code "113") (name "Net-(U14-LED7)") (class "Default")
      (node (ref "L8") (pin "2") (pinfunction "2_2") (pintype "unspecified"))
      (node (ref "U14") (pin "13") (pinfunction "LED7_13") (pintype "unspecified"))
    )
    (net (code "114") (name "Net-(U14-LED8)") (class "Default")
      (node (ref "L9") (pin "1") (pinfunction "1_1") (pintype "unspecified"))
      (node (ref "U14") (pin "15") (pinfunction "LED8_15") (pintype "unspecified"))
    )
    (net (code "115") (name "Net-(U14-LED9)") (class "Default")
      (node (ref "L10") (pin "1") (pinfunction "1_1") (pintype "unspecified"))
      (node (ref "U14") (pin "16") (pinfunction "LED9_16") (pintype "unspecified"))
    )
    (net (code "116") (name "Net-(U14-LED10)") (class "Default")
      (node (ref "L11") (pin "1") (pinfunction "1_1") (pintype "unspecified"))
      (node (ref "U14") (pin "17") (pinfunction "LED10_17") (pintype "unspecified"))
    )
    (net (code "117") (name "Net-(U14-LED11)") (class "Default")
      (node (ref "L12") (pin "1") (pinfunction "1_1") (pintype "unspecified"))
      (node (ref "U14") (pin "18") (pinfunction "LED11_18") (pintype "unspecified"))
    )
    (net (code "118") (name "Net-(U14-LED12)") (class "Default")
      (node (ref "L13") (pin "1") (pinfunction "1_1") (pintype "unspecified"))
      (node (ref "U14") (pin "19") (pinfunction "LED12_19") (pintype "unspecified"))
    )
    (net (code "119") (name "Net-(U14-LED13)") (class "Default")
      (node (ref "L14") (pin "1") (pinfunction "1_1") (pintype "unspecified"))
      (node (ref "U14") (pin "20") (pinfunction "LED13_20") (pintype "unspecified"))
    )
    (net (code "120") (name "Net-(U14-LED14)") (class "Default")
      (node (ref "L15") (pin "1") (pinfunction "1_1") (pintype "unspecified"))
      (node (ref "U14") (pin "21") (pinfunction "LED14_21") (pintype "unspecified"))
    )
    (net (code "121") (name "Net-(U14-LED15)") (class "Default")
      (node (ref "L16") (pin "1") (pinfunction "1_1") (pintype "unspecified"))
      (node (ref "U14") (pin "22") (pinfunction "LED15_22") (pintype "unspecified"))
    )
    (net (code "122") (name "Net-(U14-OE#)") (class "Default")
      (node (ref "R4") (pin "1") (pinfunction "1_1") (pintype "input"))
      (node (ref "U14") (pin "23") (pinfunction "OE#_23") (pintype "unspecified"))
    )
    (net (code "123") (name "RST") (class "Default")
      (node (ref "CN2") (pin "10") (pinfunction "10_10") (pintype "unspecified"))
      (node (ref "MASTER") (pin "10") (pinfunction "Rst@1_10") (pintype "unspecified"))
      (node (ref "R1") (pin "1") (pinfunction "1_1") (pintype "unspecified"))
    )
    (net (code "124") (name "RST{slash}USB") (class "Default")
      (node (ref "MASTER") (pin "73") (pinfunction "*D46_73") (pintype "unspecified"))
      (node (ref "U9") (pin "4") (pinfunction "A3_4") (pintype "unspecified"))
    )
    (net (code "125") (name "RXmanette") (class "Default")
      (node (ref "MANETTE") (pin "1") (pinfunction "1_1") (pintype "unspecified"))
      (node (ref "MASTER") (pin "27") (pinfunction "D16_(TX2)_27") (pintype "unspecified"))
    )
    (net (code "126") (name "SCK") (class "Default")
      (node (ref "MASTER") (pin "79") (pinfunction "D52_79") (pintype "unspecified"))
      (node (ref "U9") (pin "9") (pinfunction "A8_9") (pintype "unspecified"))
    )
    (net (code "127") (name "SCL") (class "Default")
      (node (ref "MASTER") (pin "32") (pinfunction "D21_32") (pintype "unspecified"))
      (node (ref "R2") (pin "1") (pinfunction "1_1") (pintype "unspecified"))
      (node (ref "U1") (pin "3") (pinfunction "SCL_3") (pintype "unspecified"))
      (node (ref "U14") (pin "26") (pinfunction "SCL_26") (pintype "unspecified"))
    )
    (net (code "128") (name "SDA") (class "Default")
      (node (ref "MASTER") (pin "31") (pinfunction "D20_31") (pintype "unspecified"))
      (node (ref "R3") (pin "1") (pinfunction "1_1") (pintype "unspecified"))
      (node (ref "U1") (pin "4") (pinfunction "SDA_4") (pintype "unspecified"))
      (node (ref "U14") (pin "27") (pinfunction "SDA_27") (pintype "unspecified"))
    )
    (net (code "129") (name "SS{slash}RF") (class "Default")
      (node (ref "MASTER") (pin "74") (pinfunction "D47_74") (pintype "unspecified"))
      (node (ref "U9") (pin "3") (pinfunction "A2_3") (pintype "unspecified"))
    )
    (net (code "130") (name "SS{slash}USB") (class "Default")
      (node (ref "MASTER") (pin "75") (pinfunction "D48_75") (pintype "unspecified"))
      (node (ref "U9") (pin "6") (pinfunction "A5_6") (pintype "unspecified"))
    )
    (net (code "131") (name "Score{slash}CLK") (class "Default")
      (node (ref "MASTER") (pin "43") (pinfunction "A0_43") (pintype "unspecified"))
      (node (ref "SCORE1") (pin "1") (pinfunction "CLK_1") (pintype "unspecified"))
      (node (ref "SCORE2") (pin "1") (pinfunction "CLK_1") (pintype "unspecified"))
      (node (ref "SCORE3") (pin "1") (pinfunction "CLK_1") (pintype "unspecified"))
    )
    (net (code "132") (name "Score{slash}DIO") (class "Default")
      (node (ref "MASTER") (pin "44") (pinfunction "A1_44") (pintype "unspecified"))
      (node (ref "SCORE1") (pin "2") (pinfunction "DIO_2") (pintype "unspecified"))
      (node (ref "SCORE2") (pin "2") (pinfunction "DIO_2") (pintype "unspecified"))
      (node (ref "SCORE3") (pin "2") (pinfunction "DIO_2") (pintype "unspecified"))
    )
    (net (code "133") (name "TXmanette") (class "Default")
      (node (ref "MANETTE") (pin "2") (pinfunction "2_2") (pintype "unspecified"))
      (node (ref "MASTER") (pin "28") (pinfunction "D17_(RX2)_28") (pintype "unspecified"))
    )
    (net (code "134") (name "VCC") (class "Default")
      (node (ref "C1") (pin "1") (pinfunction "1_1") (pintype "unspecified"))
      (node (ref "C6") (pin "1") (pinfunction "1_1") (pintype "unspecified"))
      (node (ref "C7") (pin "1") (pinfunction "1_1") (pintype "unspecified"))
      (node (ref "C8") (pin "1") (pinfunction "1_1") (pintype "unspecified"))
      (node (ref "C9") (pin "1") (pinfunction "1_1") (pintype "unspecified"))
      (node (ref "J1") (pin "1") (pinfunction "1_1") (pintype "bidirectional"))
      (node (ref "J1") (pin "3") (pinfunction "3_3") (pintype "bidirectional"))
      (node (ref "R5") (pin "1") (pinfunction "1_1") (pintype "unspecified"))
      (node (ref "U2") (pin "2") (pinfunction "VI_2") (pintype "passive"))
      (node (ref "U3") (pin "2") (pinfunction "VI_2") (pintype "passive"))
      (node (ref "U6") (pin "2") (pinfunction "VI_2") (pintype "passive"))
      (node (ref "U7") (pin "2") (pinfunction "VI_2") (pintype "passive"))
    )
    (net (code "135") (name "unconnected-(CN1-Pad1)") (class "Default")
      (node (ref "CN1") (pin "1") (pinfunction "1_1") (pintype "unspecified"))
    )
    (net (code "136") (name "unconnected-(CN1-Pad2)") (class "Default")
      (node (ref "CN1") (pin "2") (pinfunction "2_2") (pintype "unspecified"))
    )
    (net (code "137") (name "unconnected-(CN1-Pad3)") (class "Default")
      (node (ref "CN1") (pin "3") (pinfunction "3_3") (pintype "unspecified"))
    )
    (net (code "138") (name "unconnected-(CN1-Pad4)") (class "Default")
      (node (ref "CN1") (pin "4") (pinfunction "4_4") (pintype "unspecified"))
    )
    (net (code "139") (name "unconnected-(CN1-Pad5)") (class "Default")
      (node (ref "CN1") (pin "5") (pinfunction "5_5") (pintype "unspecified"))
    )
    (net (code "140") (name "unconnected-(CN1-Pad6)") (class "Default")
      (node (ref "CN1") (pin "6") (pinfunction "6_6") (pintype "unspecified"))
    )
    (net (code "141") (name "unconnected-(CN1-Pad7)") (class "Default")
      (node (ref "CN1") (pin "7") (pinfunction "7_7") (pintype "unspecified"))
    )
    (net (code "142") (name "unconnected-(CN1-Pad8)") (class "Default")
      (node (ref "CN1") (pin "8") (pinfunction "8_8") (pintype "unspecified"))
    )
    (net (code "143") (name "unconnected-(CN1-Pad9)") (class "Default")
      (node (ref "CN1") (pin "9") (pinfunction "9_9") (pintype "unspecified"))
    )
    (net (code "144") (name "unconnected-(CN1-Pad10)") (class "Default")
      (node (ref "CN1") (pin "10") (pinfunction "10_10") (pintype "unspecified"))
    )
    (net (code "145") (name "unconnected-(M1-IRQ-Pad8)") (class "Default")
      (node (ref "M1") (pin "8") (pinfunction "IRQ_8") (pintype "unspecified"))
    )
    (net (code "146") (name "unconnected-(MASTER-*D2-Pad13)") (class "Default")
      (node (ref "MASTER") (pin "13") (pinfunction "*D2_13") (pintype "unspecified"))
    )
    (net (code "147") (name "unconnected-(MASTER-*D3-Pad14)") (class "Default")
      (node (ref "MASTER") (pin "14") (pinfunction "*D3_14") (pintype "unspecified"))
    )
    (net (code "148") (name "unconnected-(MASTER-*D13-Pad24)") (class "Default")
      (node (ref "MASTER") (pin "24") (pinfunction "*D13_24") (pintype "unspecified"))
    )
    (net (code "149") (name "unconnected-(MASTER-A8-Pad51)") (class "Default")
      (node (ref "MASTER") (pin "51") (pinfunction "A8_51") (pintype "unspecified"))
    )
    (net (code "150") (name "unconnected-(MASTER-A9-Pad52)") (class "Default")
      (node (ref "MASTER") (pin "52") (pinfunction "A9_52") (pintype "unspecified"))
    )
    (net (code "151") (name "unconnected-(MASTER-A10-Pad53)") (class "Default")
      (node (ref "MASTER") (pin "53") (pinfunction "A10_53") (pintype "unspecified"))
    )
    (net (code "152") (name "unconnected-(MASTER-A11-Pad54)") (class "Default")
      (node (ref "MASTER") (pin "54") (pinfunction "A11_54") (pintype "unspecified"))
    )
    (net (code "153") (name "unconnected-(MASTER-A12-Pad55)") (class "Default")
      (node (ref "MASTER") (pin "55") (pinfunction "A12_55") (pintype "unspecified"))
    )
    (net (code "154") (name "unconnected-(MASTER-A13-Pad56)") (class "Default")
      (node (ref "MASTER") (pin "56") (pinfunction "A13_56") (pintype "unspecified"))
    )
    (net (code "155") (name "unconnected-(MASTER-A14-Pad57)") (class "Default")
      (node (ref "MASTER") (pin "57") (pinfunction "A14_57") (pintype "unspecified"))
    )
    (net (code "156") (name "unconnected-(MASTER-ARef-Pad9)") (class "Default")
      (node (ref "MASTER") (pin "9") (pinfunction "ARef_9") (pintype "unspecified"))
    )
    (net (code "157") (name "unconnected-(MASTER-D18(Tx1)INT-Pad29)") (class "Default")
      (node (ref "MASTER") (pin "29") (pinfunction "D18(Tx1)INT_29") (pintype "unspecified"))
    )
    (net (code "158") (name "unconnected-(MASTER-D19(Rx1)INT-Pad30)") (class "Default")
      (node (ref "MASTER") (pin "30") (pinfunction "D19(Rx1)INT_30") (pintype "unspecified"))
    )
    (net (code "159") (name "unconnected-(MASTER-D22-Pad33)") (class "Default")
      (node (ref "MASTER") (pin "33") (pinfunction "D22_33") (pintype "unspecified"))
    )
    (net (code "160") (name "unconnected-(MASTER-D23-Pad34)") (class "Default")
      (node (ref "MASTER") (pin "34") (pinfunction "D23_34") (pintype "unspecified"))
    )
    (net (code "161") (name "unconnected-(MASTER-D32-Pad59)") (class "Default")
      (node (ref "MASTER") (pin "59") (pinfunction "D32_59") (pintype "unspecified"))
    )
    (net (code "162") (name "unconnected-(MASTER-D33-Pad60)") (class "Default")
      (node (ref "MASTER") (pin "60") (pinfunction "D33_60") (pintype "unspecified"))
    )
    (net (code "163") (name "unconnected-(MASTER-D34-Pad61)") (class "Default")
      (node (ref "MASTER") (pin "61") (pinfunction "D34_61") (pintype "unspecified"))
    )
    (net (code "164") (name "unconnected-(MASTER-D35-Pad62)") (class "Default")
      (node (ref "MASTER") (pin "62") (pinfunction "D35_62") (pintype "unspecified"))
    )
    (net (code "165") (name "unconnected-(MASTER-D36-Pad63)") (class "Default")
      (node (ref "MASTER") (pin "63") (pinfunction "D36_63") (pintype "unspecified"))
    )
    (net (code "166") (name "unconnected-(MASTER-D37-Pad64)") (class "Default")
      (node (ref "MASTER") (pin "64") (pinfunction "D37_64") (pintype "unspecified"))
    )
    (net (code "167") (name "unconnected-(MASTER-D38-Pad65)") (class "Default")
      (node (ref "MASTER") (pin "65") (pinfunction "D38_65") (pintype "unspecified"))
    )
    (net (code "168") (name "unconnected-(MASTER-D39-Pad66)") (class "Default")
      (node (ref "MASTER") (pin "66") (pinfunction "D39_66") (pintype "unspecified"))
    )
    (net (code "169") (name "unconnected-(MASTER-D40-Pad67)") (class "Default")
      (node (ref "MASTER") (pin "67") (pinfunction "D40_67") (pintype "unspecified"))
    )
    (net (code "170") (name "unconnected-(MASTER-D41-Pad68)") (class "Default")
      (node (ref "MASTER") (pin "68") (pinfunction "D41_68") (pintype "unspecified"))
    )
    (net (code "171") (name "unconnected-(MASTER-D42-Pad69)") (class "Default")
      (node (ref "MASTER") (pin "69") (pinfunction "D42_69") (pintype "unspecified"))
    )
    (net (code "172") (name "unconnected-(MASTER-D43-Pad70)") (class "Default")
      (node (ref "MASTER") (pin "70") (pinfunction "D43_70") (pintype "unspecified"))
    )
    (net (code "173") (name "unconnected-(MASTER-Rx_(D0)-Pad11)") (class "Default")
      (node (ref "MASTER") (pin "11") (pinfunction "Rx_(D0)_11") (pintype "unspecified"))
    )
    (net (code "174") (name "unconnected-(MASTER-Tx(D1)-Pad12)") (class "Default")
      (node (ref "MASTER") (pin "12") (pinfunction "Tx(D1)_12") (pintype "unspecified"))
    )
    (net (code "175") (name "unconnected-(U1-DRDY-Pad5)") (class "Default")
      (node (ref "U1") (pin "5") (pinfunction "DRDY_5") (pintype "unspecified"))
    )
    (net (code "176") (name "unconnected-(U4-EN-Pad1)") (class "Default")
      (node (ref "U4") (pin "1") (pinfunction "EN_1") (pintype "unspecified"))
    )
    (net (code "177") (name "unconnected-(U4-STATE-Pad6)") (class "Default")
      (node (ref "U4") (pin "6") (pinfunction "STATE_6") (pintype "unspecified"))
    )
    (net (code "178") (name "unconnected-(U9-A1-Pad1)") (class "Default")
      (node (ref "U9") (pin "1") (pinfunction "A1_1") (pintype "unspecified"))
    )
    (net (code "179") (name "unconnected-(U9-B1-Pad20)") (class "Default")
      (node (ref "U9") (pin "20") (pinfunction "B1_20") (pintype "unspecified"))
    )
    (net (code "180") (name "unconnected-(U9-OE-Pad10)") (class "Default")
      (node (ref "U9") (pin "10") (pinfunction "OE_10") (pintype "unspecified"))
    )
    (net (code "181") (name "unconnected-(U10-RAW-Pad24)") (class "Default")
      (node (ref "U10") (pin "24") (pinfunction "RAW_24") (pintype "unspecified"))
    )
  )
)
